# SCH_Power-Controller_2025-03-20.net
KiCad netlist of a schematic drawn in EasyEDA
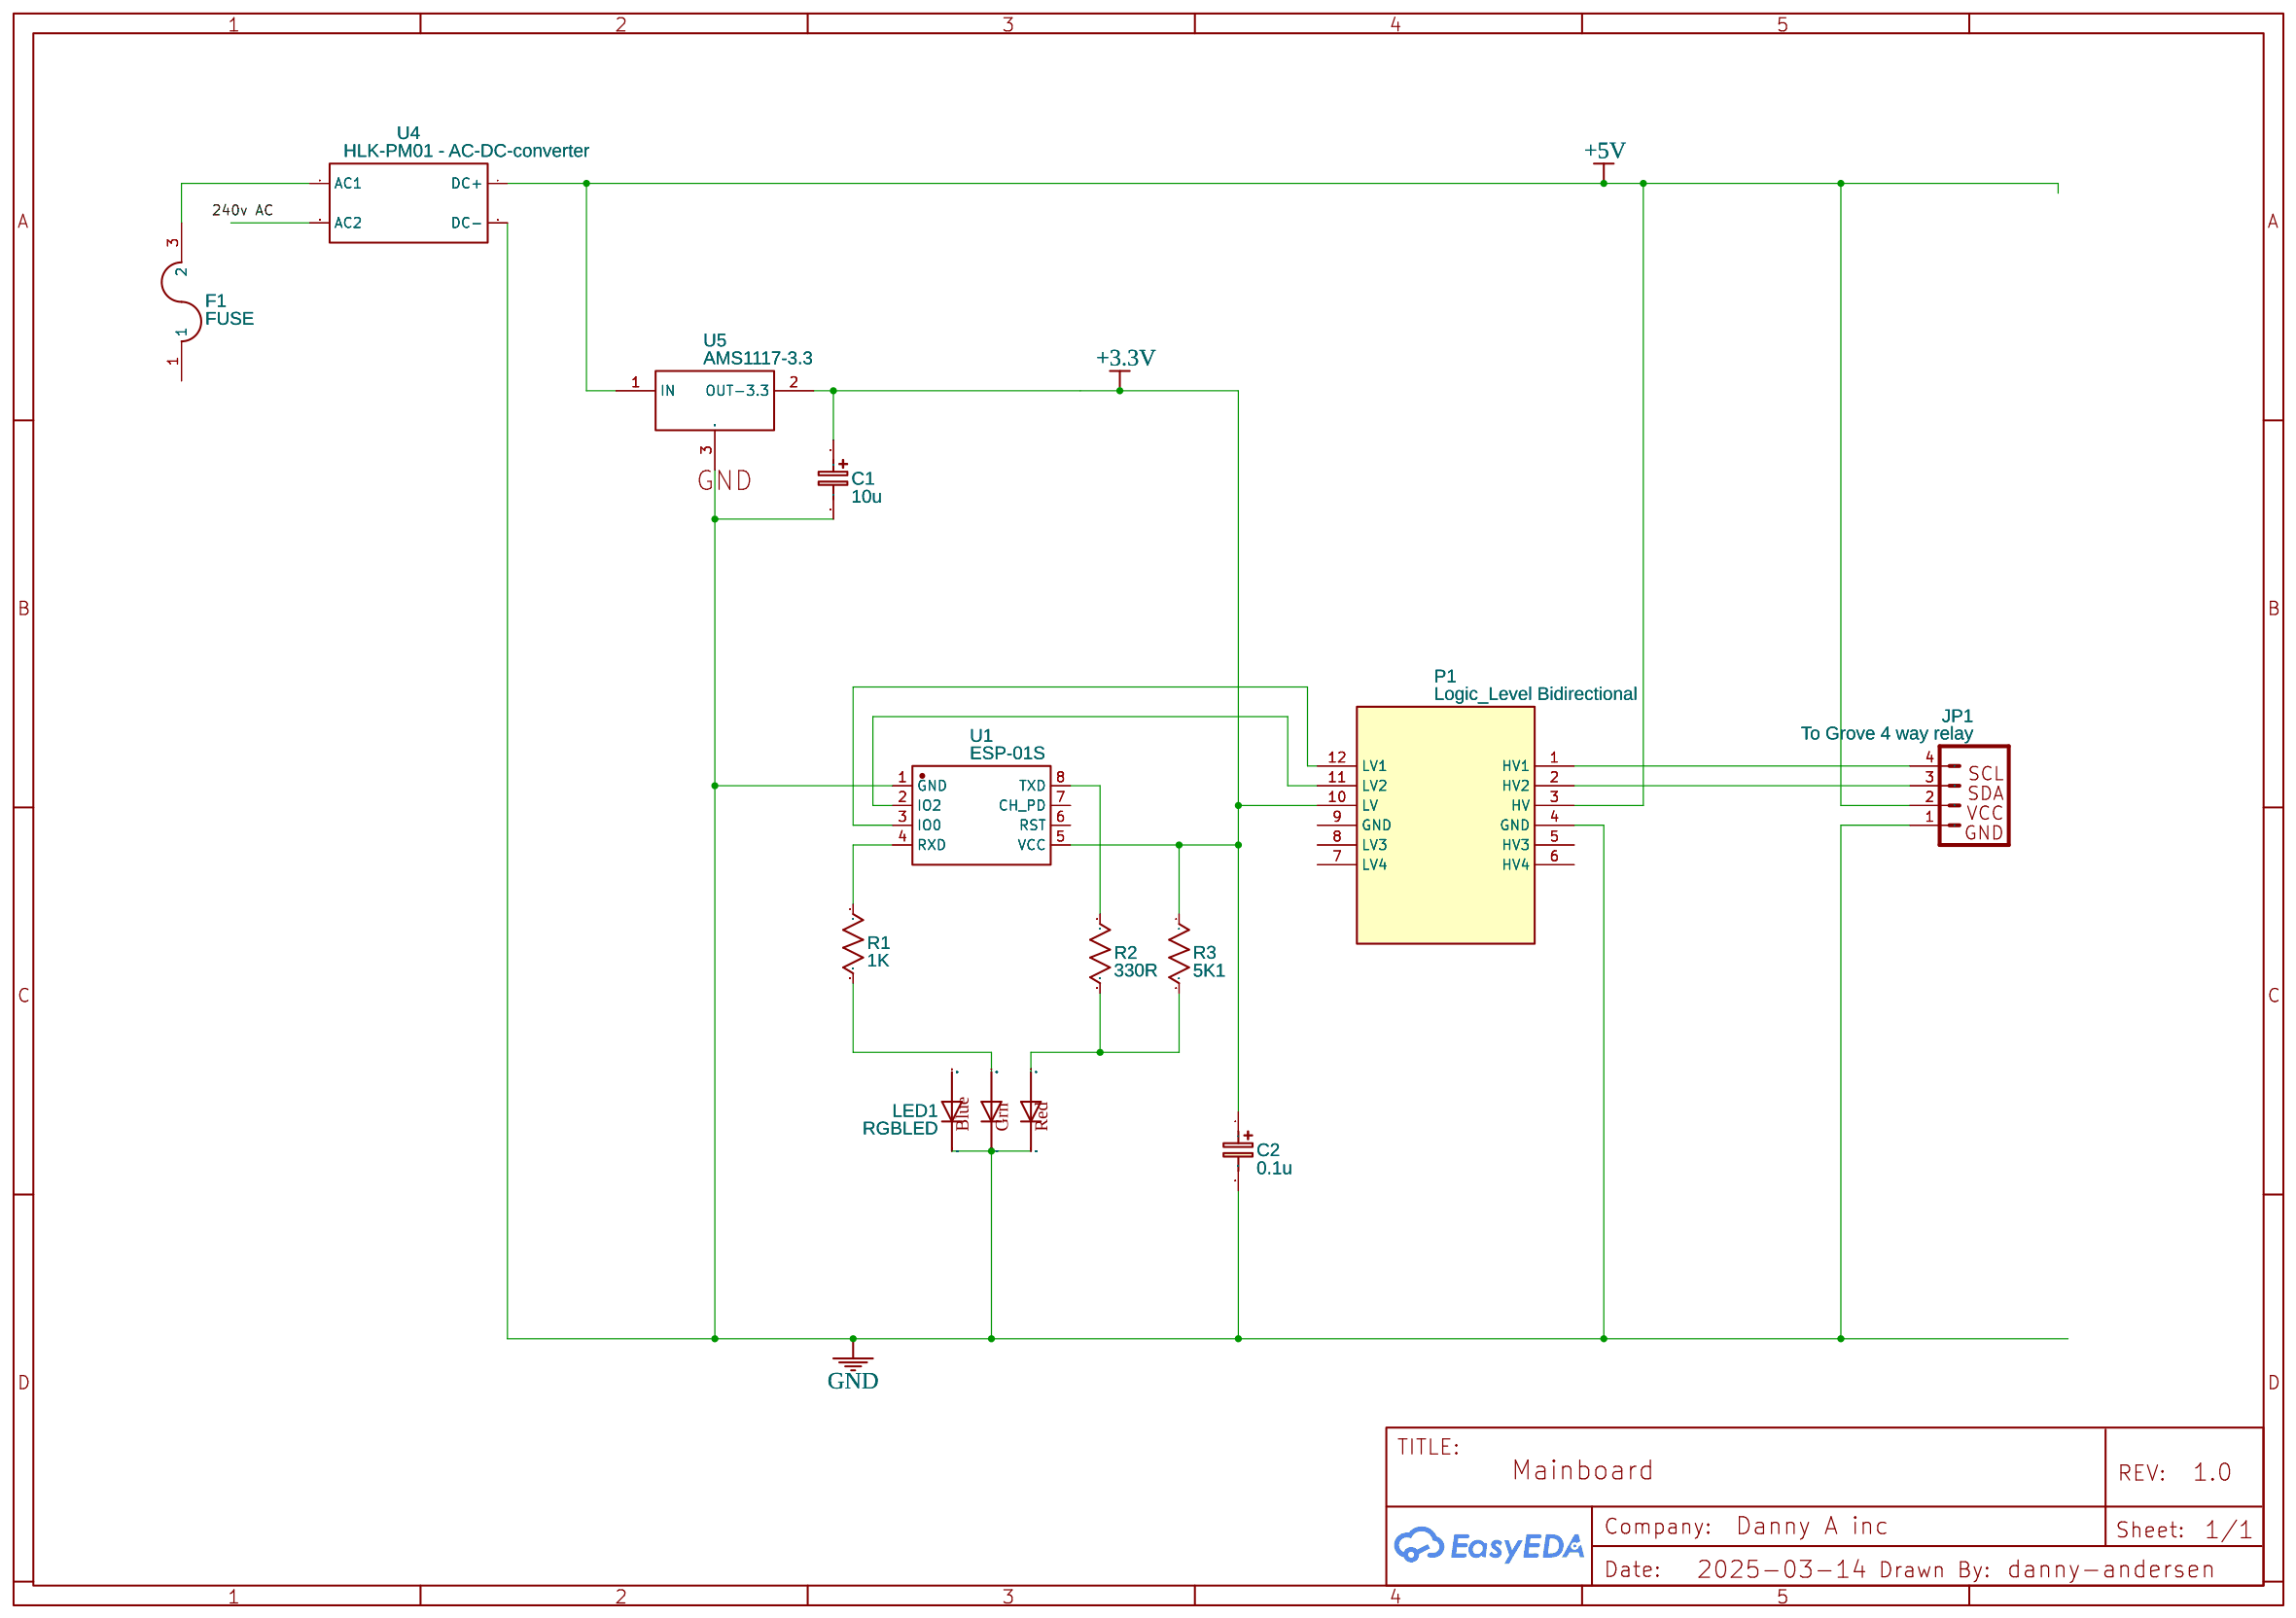
[diagram p0: schematic sheet]

(export (version "E")
  (design (tool "Eeschema 10.0.6"))
  (components
    (comp (ref "C1") (value "10u") (libsource (lib "") (part "C_Tan_SMD_A_EU")))
    (comp (ref "C2") (value "0.1u") (libsource (lib "") (part "C_Tan_SMD_A_EU_1")))
    (comp (ref "F1")
      (value "FUSE")
      (fields (field (name "Manufacturer Part") "?"))
      (libsource (lib "") (part "Unknown_85_-660"))
    )
    (comp (ref "JP1") (value "To Grove 4 way relay") (libsource (lib "") (part "I2C_STANDARD")))
    (comp (ref "LED1") (value "RGBLED") (libsource (lib "") (part "RGBLED")))
    (comp (ref "P1")
      (value "Logic_Level Bidirectional")
      (libsource (lib "") (part "Logic_Level Bidirectional"))
    )
    (comp (ref "R1") (value "1K") (libsource (lib "") (part "R_0603_US")))
    (comp (ref "R2") (value "330R") (libsource (lib "") (part "R_0603_US")))
    (comp (ref "R3") (value "5K1") (libsource (lib "") (part "R_0603_US")))
    (comp (ref "U1")
      (value "ESP-01S")
      (fields (field (name "Manufacturer") "Ai-Thinker"))
      (libsource (lib "") (part "ESP-01S"))
    )
    (comp (ref "U4")
      (value "HLK-PM01 - AC-DC-converter")
      (fields (field (name "Manufacturer Part") "?"))
      (libsource (lib "") (part "Unknown_190_-710"))
    )
    (comp (ref "U5")
      (value "AMS1117-3.3")
      (fields (field (name "Manufacturer Part") "CJ78L05") (field (name "Manufacturer") "CJ"))
      (libsource (lib "") (part "7805(SOT-89)"))
    )
  )
  (nets
    (net (code "1") (name "+3.3V") (class "Default")
      (node (ref "C1") (pin "1") (pinfunction "1_1") (pintype "unspecified"))
      (node (ref "C2") (pin "1") (pinfunction "1_1") (pintype "unspecified"))
      (node (ref "P1") (pin "10") (pinfunction "LV_10") (pintype "unspecified"))
      (node (ref "R3") (pin "1") (pinfunction "1_1") (pintype "unspecified"))
      (node (ref "U1") (pin "5") (pinfunction "VCC_5") (pintype "unspecified"))
      (node (ref "U5") (pin "2") (pinfunction "OUT-3.3_2") (pintype "passive"))
    )
    (net (code "2") (name "+5V") (class "Default")
      (node (ref "JP1") (pin "2") (pinfunction "2_2") (pintype "unspecified"))
      (node (ref "P1") (pin "3") (pinfunction "HV_3") (pintype "unspecified"))
      (node (ref "U4") (pin "4") (pinfunction "DC+_4") (pintype "unspecified"))
      (node (ref "U5") (pin "1") (pinfunction "IN_1") (pintype "passive"))
    )
    (net (code "4") (name "GND") (class "Default")
      (node (ref "C1") (pin "2") (pinfunction "2_2") (pintype "unspecified"))
      (node (ref "C2") (pin "2") (pinfunction "2_2") (pintype "unspecified"))
      (node (ref "JP1") (pin "1") (pinfunction "1_1") (pintype "unspecified"))
      (node (ref "LED1") (pin "4") (pinfunction "BLUE_C_4") (pintype "unspecified"))
      (node (ref "LED1") (pin "5") (pinfunction "RED_C_5") (pintype "unspecified"))
      (node (ref "LED1") (pin "6") (pinfunction "GREEN_C_6") (pintype "unspecified"))
      (node (ref "P1") (pin "4") (pinfunction "GND_4") (pintype "unspecified"))
      (node (ref "U1") (pin "1") (pinfunction "GND_1") (pintype "unspecified"))
      (node (ref "U4") (pin "3") (pinfunction "DC-_3") (pintype "unspecified"))
      (node (ref "U5") (pin "3") (pinfunction "GND_3") (pintype "passive"))
    )
    (net (code "5") (name "Net-(F1-2)") (class "Default")
      (node (ref "F1") (pin "3") (pinfunction "2_3") (pintype "unspecified"))
      (node (ref "U4") (pin "1") (pinfunction "AC1_1") (pintype "input"))
    )
    (net (code "6") (name "Net-(LED1-GREEN_A)") (class "Default")
      (node (ref "LED1") (pin "1") (pinfunction "GREEN_A_1") (pintype "unspecified"))
      (node (ref "R1") (pin "2") (pinfunction "2_2") (pintype "unspecified"))
    )
    (net (code "7") (name "Net-(LED1-RED_A)") (class "Default")
      (node (ref "LED1") (pin "2") (pinfunction "RED_A_2") (pintype "unspecified"))
      (node (ref "R2") (pin "2") (pinfunction "2_2") (pintype "unspecified"))
      (node (ref "R3") (pin "2") (pinfunction "2_2") (pintype "unspecified"))
    )
    (net (code "8") (name "Net-(P1-HV1)") (class "Default")
      (node (ref "JP1") (pin "4") (pinfunction "4_4") (pintype "unspecified"))
      (node (ref "P1") (pin "1") (pinfunction "HV1_1") (pintype "unspecified"))
    )
    (net (code "9") (name "Net-(P1-HV2)") (class "Default")
      (node (ref "JP1") (pin "3") (pinfunction "3_3") (pintype "unspecified"))
      (node (ref "P1") (pin "2") (pinfunction "HV2_2") (pintype "unspecified"))
    )
    (net (code "10") (name "Net-(P1-LV1)") (class "Default")
      (node (ref "P1") (pin "12") (pinfunction "LV1_12") (pintype "unspecified"))
      (node (ref "U1") (pin "3") (pinfunction "IO0_3") (pintype "unspecified"))
    )
    (net (code "11") (name "Net-(P1-LV2)") (class "Default")
      (node (ref "P1") (pin "11") (pinfunction "LV2_11") (pintype "unspecified"))
      (node (ref "U1") (pin "2") (pinfunction "IO2_2") (pintype "unspecified"))
    )
    (net (code "12") (name "Net-(U1-RXD)") (class "Default")
      (node (ref "R1") (pin "1") (pinfunction "1_1") (pintype "unspecified"))
      (node (ref "U1") (pin "4") (pinfunction "RXD_4") (pintype "unspecified"))
    )
    (net (code "13") (name "Net-(U1-TXD)") (class "Default")
      (node (ref "R2") (pin "1") (pinfunction "1_1") (pintype "unspecified"))
      (node (ref "U1") (pin "8") (pinfunction "TXD_8") (pintype "unspecified"))
    )
    (net (code "14") (name "unconnected-(F1-Pad1)") (class "Default")
      (node (ref "F1") (pin "1") (pinfunction "1_1") (pintype "unspecified"))
    )
    (net (code "15") (name "unconnected-(LED1-BLUE_A-Pad3)") (class "Default")
      (node (ref "LED1") (pin "3") (pinfunction "BLUE_A_3") (pintype "unspecified"))
    )
    (net (code "16") (name "unconnected-(P1-GND-Pad9)") (class "Default")
      (node (ref "P1") (pin "9") (pinfunction "GND_9") (pintype "unspecified"))
    )
    (net (code "17") (name "unconnected-(P1-HV3-Pad5)") (class "Default")
      (node (ref "P1") (pin "5") (pinfunction "HV3_5") (pintype "unspecified"))
    )
    (net (code "18") (name "unconnected-(P1-HV4-Pad6)") (class "Default")
      (node (ref "P1") (pin "6") (pinfunction "HV4_6") (pintype "unspecified"))
    )
    (net (code "19") (name "unconnected-(P1-LV3-Pad8)") (class "Default")
      (node (ref "P1") (pin "8") (pinfunction "LV3_8") (pintype "unspecified"))
    )
    (net (code "20") (name "unconnected-(P1-LV4-Pad7)") (class "Default")
      (node (ref "P1") (pin "7") (pinfunction "LV4_7") (pintype "unspecified"))
    )
    (net (code "21") (name "unconnected-(U1-CH_PD-Pad7)") (class "Default")
      (node (ref "U1") (pin "7") (pinfunction "CH_PD_7") (pintype "unspecified"))
    )
    (net (code "22") (name "unconnected-(U1-RST-Pad6)") (class "Default")
      (node (ref "U1") (pin "6") (pinfunction "RST_6") (pintype "unspecified"))
    )
    (net (code "23") (name "unconnected-(U4-AC2-Pad2)") (class "Default")
      (node (ref "U4") (pin "2") (pinfunction "AC2_2") (pintype "input"))
    )
  )
)
